# SCH_USB_HUB1_2025-02-07.net
KiCad netlist of a schematic drawn in EasyEDA
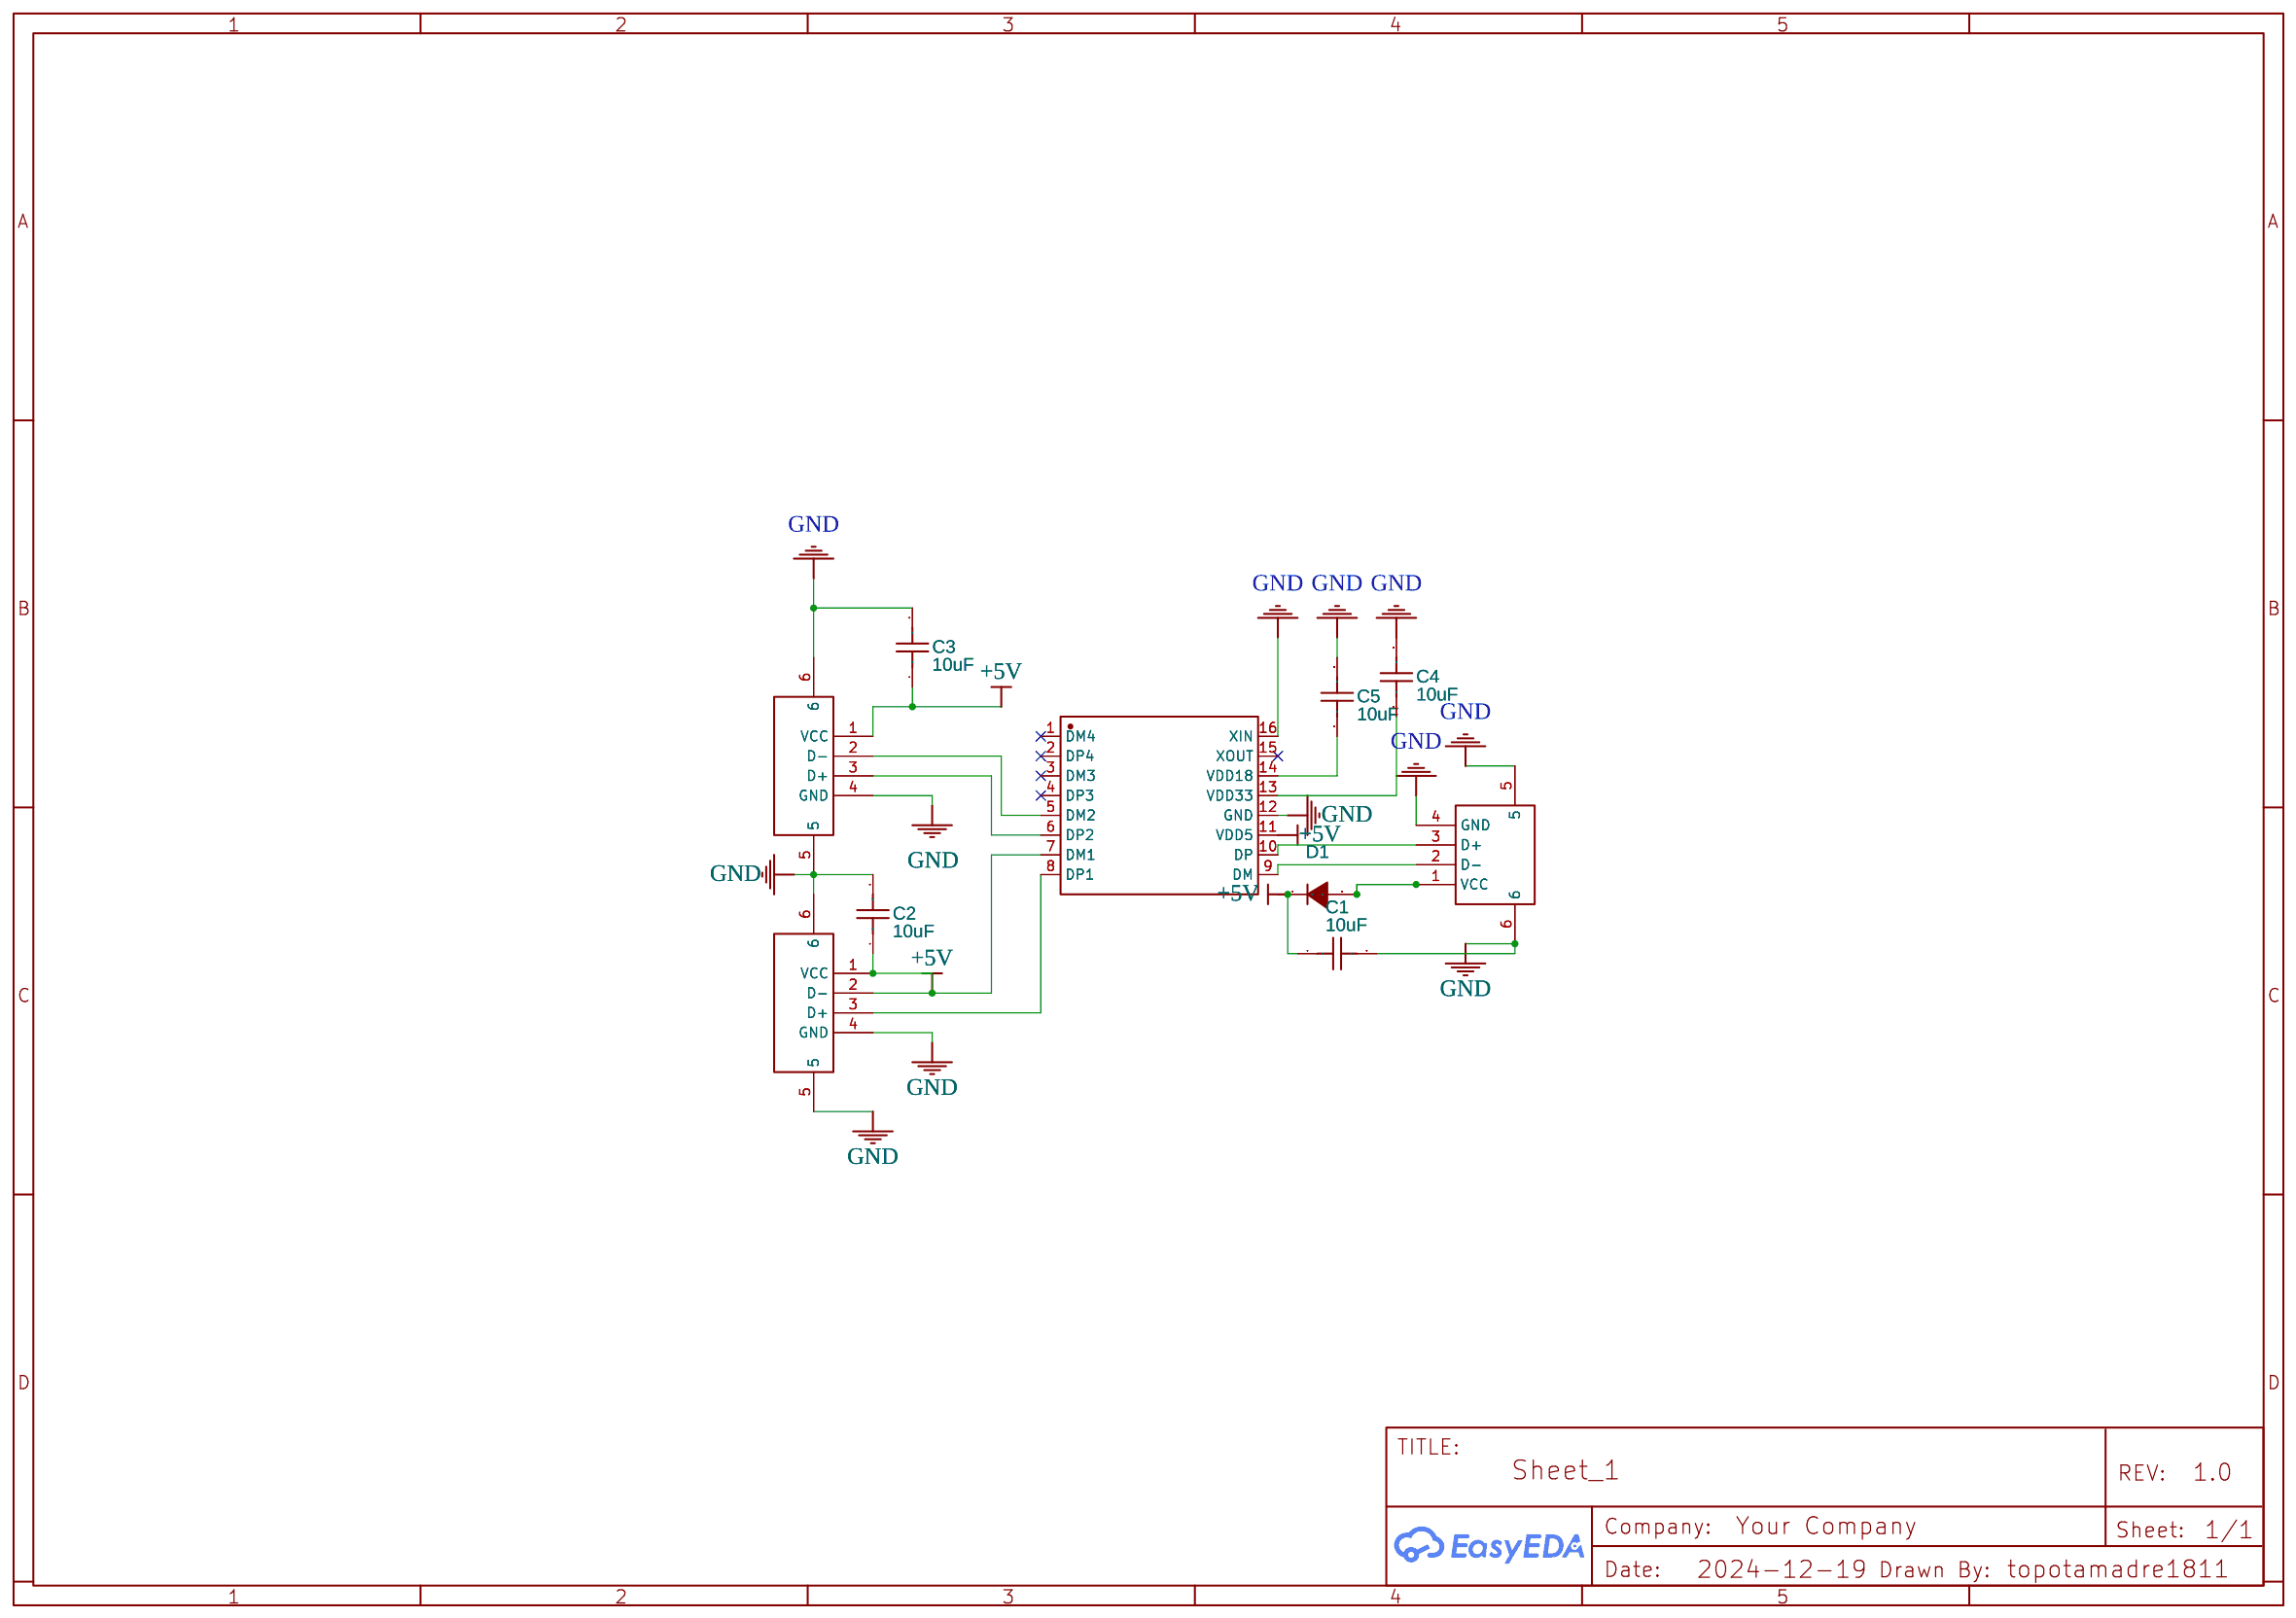
[diagram p0: schematic sheet]

(export (version "E")
  (design (tool "Eeschema 10.0.6"))
  (components
    (comp (ref "C1")
      (value "10uF")
      (fields
        (field (name "Manufacturer Part") "CL10A106KP8NNNC")
        (field (name "Manufacturer") "SAMSUNG(三星)")
      )
      (libsource (lib "") (part "CL10A106KP8NNNC_1"))
    )
    (comp (ref "C2")
      (value "10uF")
      (fields
        (field (name "Manufacturer Part") "CL10A106KP8NNNC")
        (field (name "Manufacturer") "SAMSUNG(三星)")
      )
      (libsource (lib "") (part "CL10A106KP8NNNC"))
    )
    (comp (ref "C3")
      (value "10uF")
      (fields
        (field (name "Manufacturer Part") "CL10A106KP8NNNC")
        (field (name "Manufacturer") "SAMSUNG(三星)")
      )
      (libsource (lib "") (part "CL10A106KP8NNNC"))
    )
    (comp (ref "C4")
      (value "10uF")
      (fields
        (field (name "Manufacturer Part") "CL10A106KP8NNNC")
        (field (name "Manufacturer") "SAMSUNG(三星)")
      )
      (libsource (lib "") (part "CL10A106KP8NNNC"))
    )
    (comp (ref "C5")
      (value "10uF")
      (fields
        (field (name "Manufacturer Part") "CL10A106KP8NNNC")
        (field (name "Manufacturer") "SAMSUNG(三星)")
      )
      (libsource (lib "") (part "CL10A106KP8NNNC"))
    )
    (comp (ref "D1")
      (value "NSR0320MW2T1G")
      (fields (field (name "Manufacturer") "onsemi(安森美)"))
      (libsource (lib "") (part "NSR0320MW2T1G"))
    )
    (comp (ref "U1")
      (value "SL2.1A")
      (fields (field (name "Manufacturer") "CoreChips(和芯润德)"))
      (libsource (lib "") (part "SL2.1A"))
    )
    (comp (ref "USB1")
      (value "U-G-04DD-W-01")
      (fields (field (name "Manufacturer Part") "U-G-O4DD-W-1") (field (name "Manufacturer") "韩国韩荣"))
      (libsource (lib "") (part "U-G-04DD-W-01"))
    )
    (comp (ref "USB2")
      (value "USB-AF-90-14.4X13.6-H7.0-DIP")
      (fields (field (name "Manufacturer Part") "903-131A1011D10100") (field (name "Manufacturer") "精拓金"))
      (libsource (lib "") (part "USB-AF-90-14.4X13.6-H7.0-DIP"))
    )
    (comp (ref "USB3")
      (value "USB-AF-90-14.4X13.6-H7.0-DIP")
      (fields (field (name "Manufacturer Part") "903-131A1011D10100") (field (name "Manufacturer") "精拓金"))
      (libsource (lib "") (part "USB-AF-90-14.4X13.6-H7.0-DIP"))
    )
  )
  (nets
    (net (code "1") (name "+5V") (class "Default")
      (node (ref "C1") (pin "1") (pinfunction "1_1") (pintype "unspecified"))
      (node (ref "C2") (pin "1") (pinfunction "1_1") (pintype "unspecified"))
      (node (ref "C3") (pin "1") (pinfunction "1_1") (pintype "unspecified"))
      (node (ref "D1") (pin "1") (pinfunction "C_1") (pintype "unspecified"))
      (node (ref "U1") (pin "11") (pinfunction "VDD5_11") (pintype "unspecified"))
      (node (ref "U1") (pin "7") (pinfunction "DM1_7") (pintype "unspecified"))
      (node (ref "USB2") (pin "1") (pinfunction "VCC_1") (pintype "unspecified"))
      (node (ref "USB3") (pin "1") (pinfunction "VCC_1") (pintype "unspecified"))
      (node (ref "USB3") (pin "2") (pinfunction "D-_2") (pintype "unspecified"))
    )
    (net (code "2") (name "GND") (class "Default")
      (node (ref "C1") (pin "2") (pinfunction "2_2") (pintype "unspecified"))
      (node (ref "C2") (pin "2") (pinfunction "2_2") (pintype "unspecified"))
      (node (ref "C3") (pin "2") (pinfunction "2_2") (pintype "unspecified"))
      (node (ref "C4") (pin "2") (pinfunction "2_2") (pintype "unspecified"))
      (node (ref "C5") (pin "2") (pinfunction "2_2") (pintype "unspecified"))
      (node (ref "U1") (pin "12") (pinfunction "GND_12") (pintype "unspecified"))
      (node (ref "U1") (pin "16") (pinfunction "XIN_16") (pintype "unspecified"))
      (node (ref "USB1") (pin "4") (pinfunction "GND_4") (pintype "unspecified"))
      (node (ref "USB1") (pin "5") (pinfunction "5_5") (pintype "unspecified"))
      (node (ref "USB1") (pin "6") (pinfunction "6_6") (pintype "unspecified"))
      (node (ref "USB2") (pin "4") (pinfunction "GND_4") (pintype "unspecified"))
      (node (ref "USB2") (pin "5") (pinfunction "5_5") (pintype "unspecified"))
      (node (ref "USB2") (pin "6") (pinfunction "6_6") (pintype "unspecified"))
      (node (ref "USB3") (pin "4") (pinfunction "GND_4") (pintype "unspecified"))
      (node (ref "USB3") (pin "5") (pinfunction "5_5") (pintype "unspecified"))
      (node (ref "USB3") (pin "6") (pinfunction "6_6") (pintype "unspecified"))
    )
    (net (code "3") (name "Net-(D1-A)") (class "Default")
      (node (ref "D1") (pin "2") (pinfunction "A_2") (pintype "unspecified"))
      (node (ref "USB1") (pin "1") (pinfunction "VCC_1") (pintype "unspecified"))
    )
    (net (code "4") (name "Net-(U1-DM)") (class "Default")
      (node (ref "U1") (pin "9") (pinfunction "DM_9") (pintype "unspecified"))
      (node (ref "USB1") (pin "2") (pinfunction "D-_2") (pintype "unspecified"))
    )
    (net (code "5") (name "Net-(U1-DM2)") (class "Default")
      (node (ref "U1") (pin "5") (pinfunction "DM2_5") (pintype "unspecified"))
      (node (ref "USB2") (pin "2") (pinfunction "D-_2") (pintype "unspecified"))
    )
    (net (code "6") (name "Net-(U1-DP)") (class "Default")
      (node (ref "U1") (pin "10") (pinfunction "DP_10") (pintype "unspecified"))
      (node (ref "USB1") (pin "3") (pinfunction "D+_3") (pintype "unspecified"))
    )
    (net (code "7") (name "Net-(U1-DP1)") (class "Default")
      (node (ref "U1") (pin "8") (pinfunction "DP1_8") (pintype "unspecified"))
      (node (ref "USB3") (pin "3") (pinfunction "D+_3") (pintype "unspecified"))
    )
    (net (code "8") (name "Net-(U1-DP2)") (class "Default")
      (node (ref "U1") (pin "6") (pinfunction "DP2_6") (pintype "unspecified"))
      (node (ref "USB2") (pin "3") (pinfunction "D+_3") (pintype "unspecified"))
    )
    (net (code "9") (name "Net-(U1-VDD18)") (class "Default")
      (node (ref "C5") (pin "1") (pinfunction "1_1") (pintype "unspecified"))
      (node (ref "U1") (pin "14") (pinfunction "VDD18_14") (pintype "unspecified"))
    )
    (net (code "10") (name "Net-(U1-VDD33)") (class "Default")
      (node (ref "C4") (pin "1") (pinfunction "1_1") (pintype "unspecified"))
      (node (ref "U1") (pin "13") (pinfunction "VDD33_13") (pintype "unspecified"))
    )
    (net (code "11") (name "unconnected-(U1-DM3-Pad3)") (class "Default")
      (node (ref "U1") (pin "3") (pinfunction "DM3_3") (pintype "unspecified+no_connect"))
    )
    (net (code "12") (name "unconnected-(U1-DM4-Pad1)") (class "Default")
      (node (ref "U1") (pin "1") (pinfunction "DM4_1") (pintype "unspecified+no_connect"))
    )
    (net (code "13") (name "unconnected-(U1-DP3-Pad4)") (class "Default")
      (node (ref "U1") (pin "4") (pinfunction "DP3_4") (pintype "unspecified+no_connect"))
    )
    (net (code "14") (name "unconnected-(U1-DP4-Pad2)") (class "Default")
      (node (ref "U1") (pin "2") (pinfunction "DP4_2") (pintype "unspecified+no_connect"))
    )
    (net (code "15") (name "unconnected-(U1-XOUT-Pad15)") (class "Default")
      (node (ref "U1") (pin "15") (pinfunction "XOUT_15") (pintype "unspecified+no_connect"))
    )
  )
)
